# HallEffectSwitch.net
KiCad netlist of a schematic drawn in Altium Designer
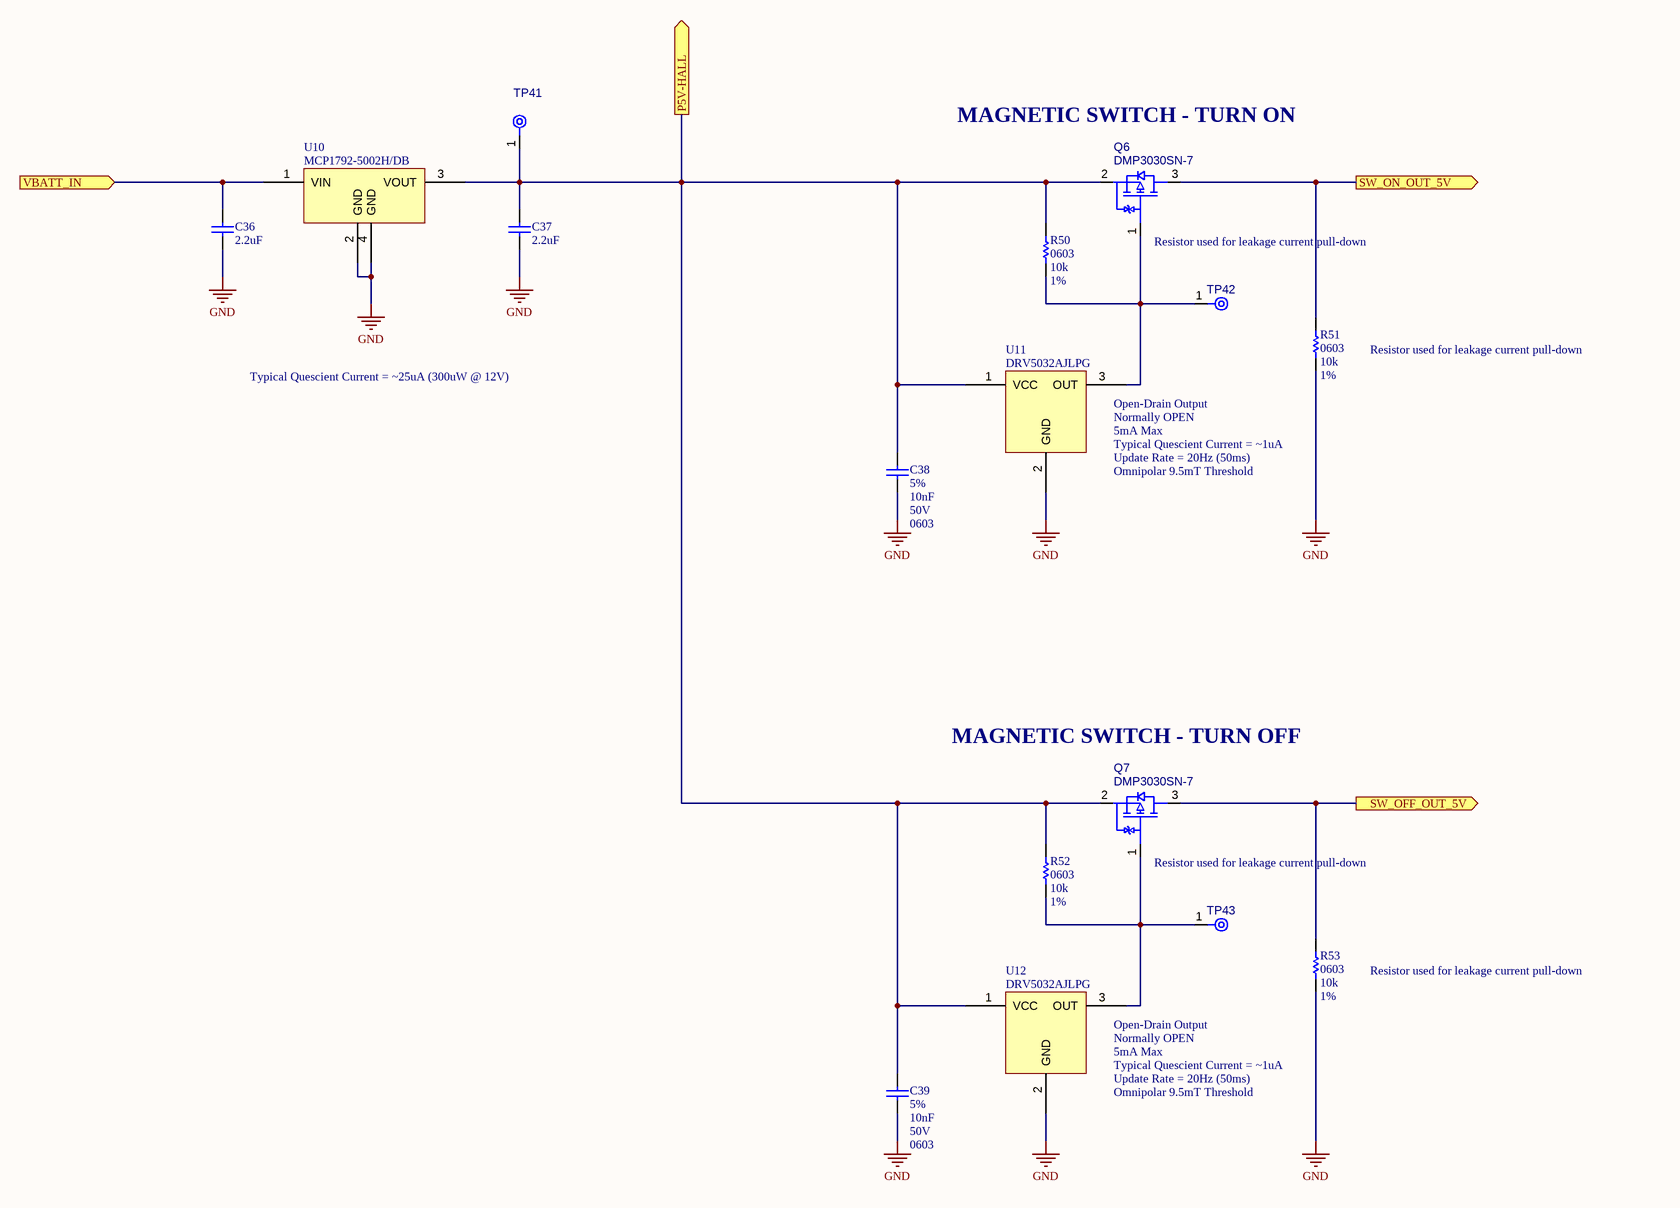
[diagram p0: HallEffectSwitch.SchDoc]

(export (version "E")
  (design (tool "Eeschema 10.0.6"))
  (components
    (comp (ref "C36")
      (value "2.2uF")
      (footprint "CAPC3225X270X30ML30")
      (description "Chip Capacitor, 2.2uF, 10%, 50 V, X7R 1210 (3225 Metric)")
      (fields (field (name "TOLERANCE") "10%") (field (name "Comment") "Capacitor 2.2uF 10%, 50V, X7R, 1210"))
      (libsource (lib "Applied Physics Lab") (part "CAP-NP-2"))
    )
    (comp (ref "C37")
      (value "2.2uF")
      (footprint "CAPC3225X270X30ML30")
      (description "Chip Capacitor, 2.2uF, 10%, 50 V, X7R 1210 (3225 Metric)")
      (fields (field (name "TOLERANCE") "10%") (field (name "Comment") "Capacitor 2.2uF 10%, 50V, X7R, 1210"))
      (libsource (lib "Applied Physics Lab") (part "CAP-NP-2"))
    )
    (comp (ref "C38")
      (value "10nF")
      (footprint "CAPC1608X90X40ML10T20")
      (description "Chip Capacitor, 10nF, +/- 5%, 50 V, C0G 0603 (1608 Metric)")
      (fields
        (field (name "TOLERANCE") "5%")
        (field (name "VOLTAGE RATING") "50V")
        (field (name "CASE/PACKAGE") "0603")
        (field (name "Comment") "Capacitor 10nF +/- 5%, 50V, C0G, 0603")
      )
      (libsource (lib "Applied Physics Lab") (part "CAP-NP-2"))
    )
    (comp (ref "C39")
      (value "10nF")
      (footprint "CAPC1608X90X40ML10T20")
      (description "Chip Capacitor, 10nF, +/- 5%, 50 V, C0G 0603 (1608 Metric)")
      (fields
        (field (name "TOLERANCE") "5%")
        (field (name "VOLTAGE RATING") "50V")
        (field (name "CASE/PACKAGE") "0603")
        (field (name "Comment") "Capacitor 10nF +/- 5%, 50V, C0G, 0603")
      )
      (libsource (lib "Applied Physics Lab") (part "CAP-NP-2"))
    )
    (comp (ref "Q6")
      (value "DMP3030SN-7")
      (footprint "SOT95P164X140-3M")
      (description "Trans Mosfet P-ch 30V 0.7A 3-PIN SC-59 T/r / Mosfet P-ch 30V 700MA SC59-3")
      (libsource (lib "Applied Physics Lab") (part "CMP-00006-6"))
    )
    (comp (ref "Q7")
      (value "DMP3030SN-7")
      (footprint "SOT95P164X140-3M")
      (description "Trans Mosfet P-ch 30V 0.7A 3-PIN SC-59 T/r / Mosfet P-ch 30V 700MA SC59-3")
      (libsource (lib "Applied Physics Lab") (part "CMP-00006-6"))
    )
    (comp (ref "R50")
      (value "10k")
      (footprint "RESC1608X55X25ML10T15")
      (description "Chip Resistor, 10 KOhm, +/- 1%, 01 W, -55 to 155 degC, 0603 (1608 Metric)")
      (fields
        (field (name "POWER") "100mW")
        (field (name "CASE/PACKAGE") "0603")
        (field (name "TOLERANCE") "1%")
        (field (name "Comment") "Resistor 10k +/-1% 0603 100 mW")
      )
      (libsource (lib "Applied Physics Lab") (part "RES-2"))
    )
    (comp (ref "R51")
      (value "10k")
      (footprint "RESC1608X55X25ML10T15")
      (description "Chip Resistor, 10 KOhm, +/- 1%, 01 W, -55 to 155 degC, 0603 (1608 Metric)")
      (fields
        (field (name "POWER") "100mW")
        (field (name "CASE/PACKAGE") "0603")
        (field (name "TOLERANCE") "1%")
        (field (name "Comment") "Resistor 10k +/-1% 0603 100 mW")
      )
      (libsource (lib "Applied Physics Lab") (part "RES-2"))
    )
    (comp (ref "R52")
      (value "10k")
      (footprint "RESC1608X55X25ML10T15")
      (description "Chip Resistor, 10 KOhm, +/- 1%, 01 W, -55 to 155 degC, 0603 (1608 Metric)")
      (fields
        (field (name "POWER") "100mW")
        (field (name "CASE/PACKAGE") "0603")
        (field (name "TOLERANCE") "1%")
        (field (name "Comment") "Resistor 10k +/-1% 0603 100 mW")
      )
      (libsource (lib "Applied Physics Lab") (part "RES-2"))
    )
    (comp (ref "R53")
      (value "10k")
      (footprint "RESC1608X55X25ML10T15")
      (description "Chip Resistor, 10 KOhm, +/- 1%, 01 W, -55 to 155 degC, 0603 (1608 Metric)")
      (fields
        (field (name "POWER") "100mW")
        (field (name "CASE/PACKAGE") "0603")
        (field (name "TOLERANCE") "1%")
        (field (name "Comment") "Resistor 10k +/-1% 0603 100 mW")
      )
      (libsource (lib "Applied Physics Lab") (part "RES-2"))
    )
    (comp (ref "TP41")
      (value "TPAD6R-CIRCLED")
      (footprint "TP06R - Circled")
      (description "0.6mm round with a silkscreen circle.")
      (libsource (lib "Applied Physics Lab") (part "CMP-001-0001-4"))
    )
    (comp (ref "TP42")
      (value "TPAD6R-CIRCLED")
      (footprint "TP06R - Circled")
      (description "0.6mm round with a silkscreen circle.")
      (libsource (lib "") (part "CMP-001-0001-4_1"))
    )
    (comp (ref "TP43")
      (value "TPAD6R-CIRCLED")
      (footprint "TP06R - Circled")
      (description "0.6mm round with a silkscreen circle.")
      (libsource (lib "") (part "CMP-001-0001-4_1"))
    )
    (comp (ref "U10")
      (value "MCP1792-5002H/DB")
      (footprint "SOT230P700X180-4M")
      (description "High input voltage regulator 5.0 V 3Ld SOT-223 3 SOT-223 TUBE RoHS Compliant: Yes")
      (libsource (lib "Applied Physics Lab") (part "MCP1792-5002H_DB-Symbol-1"))
    )
    (comp (ref "U11")
      (value "DRV5032AJLPG")
      (footprint "DRV5032ZELPGM - 500-92-US Lead Formed")
      (libsource (lib "Applied Physics Lab") (part "DRV5032ZELPGM-Symbol-1"))
    )
    (comp (ref "U12")
      (value "DRV5032AJLPG")
      (footprint "DRV5032ZELPGM - 500-92-US Lead Formed")
      (libsource (lib "Applied Physics Lab") (part "DRV5032ZELPGM-Symbol-1"))
    )
  )
  (nets
    (net (code "1") (name "/P5V-HALL") (class "Default")
      (node (ref "C37") (pin "2") (pinfunction "2_2") (pintype "passive"))
      (node (ref "C38") (pin "2") (pinfunction "2_2") (pintype "passive"))
      (node (ref "C39") (pin "2") (pinfunction "2_2") (pintype "passive"))
      (node (ref "Q6") (pin "2") (pinfunction "S_2") (pintype "passive"))
      (node (ref "Q7") (pin "2") (pinfunction "S_2") (pintype "passive"))
      (node (ref "R50") (pin "2") (pinfunction "2_2") (pintype "passive"))
      (node (ref "R52") (pin "2") (pinfunction "2_2") (pintype "passive"))
      (node (ref "TP41") (pin "1") (pinfunction "TP_1") (pintype "passive"))
      (node (ref "U10") (pin "3") (pinfunction "VOUT_3") (pintype "passive"))
      (node (ref "U11") (pin "1") (pinfunction "VCC_1") (pintype "passive"))
      (node (ref "U12") (pin "1") (pinfunction "VCC_1") (pintype "passive"))
    )
    (net (code "2") (name "/SW_OFF_OUT_5V") (class "Default")
      (node (ref "Q7") (pin "3") (pinfunction "D_3") (pintype "passive"))
      (node (ref "R53") (pin "2") (pinfunction "2_2") (pintype "passive"))
    )
    (net (code "3") (name "/SW_ON_OUT_5V") (class "Default")
      (node (ref "Q6") (pin "3") (pinfunction "D_3") (pintype "passive"))
      (node (ref "R51") (pin "2") (pinfunction "2_2") (pintype "passive"))
    )
    (net (code "4") (name "/VBATT_IN") (class "Default")
      (node (ref "C36") (pin "2") (pinfunction "2_2") (pintype "passive"))
      (node (ref "U10") (pin "1") (pinfunction "VIN_1") (pintype "passive"))
    )
    (net (code "5") (name "GND") (class "Default")
      (node (ref "C36") (pin "1") (pinfunction "1_1") (pintype "passive"))
      (node (ref "C37") (pin "1") (pinfunction "1_1") (pintype "passive"))
      (node (ref "C38") (pin "1") (pinfunction "1_1") (pintype "passive"))
      (node (ref "C39") (pin "1") (pinfunction "1_1") (pintype "passive"))
      (node (ref "R51") (pin "1") (pinfunction "1_1") (pintype "passive"))
      (node (ref "R53") (pin "1") (pinfunction "1_1") (pintype "passive"))
      (node (ref "U10") (pin "2") (pinfunction "GND_2") (pintype "passive"))
      (node (ref "U10") (pin "4") (pinfunction "GND_4") (pintype "passive"))
      (node (ref "U11") (pin "2") (pinfunction "GND_2") (pintype "passive"))
      (node (ref "U12") (pin "2") (pinfunction "GND_2") (pintype "passive"))
    )
    (net (code "6") (name "Net-(Q6-G)") (class "Default")
      (node (ref "Q6") (pin "1") (pinfunction "G_1") (pintype "passive"))
      (node (ref "R50") (pin "1") (pinfunction "1_1") (pintype "passive"))
      (node (ref "TP42") (pin "1") (pinfunction "TP_1") (pintype "passive"))
      (node (ref "U11") (pin "3") (pinfunction "OUT_3") (pintype "passive"))
    )
    (net (code "7") (name "Net-(Q7-G)") (class "Default")
      (node (ref "Q7") (pin "1") (pinfunction "G_1") (pintype "passive"))
      (node (ref "R52") (pin "1") (pinfunction "1_1") (pintype "passive"))
      (node (ref "TP43") (pin "1") (pinfunction "TP_1") (pintype "passive"))
      (node (ref "U12") (pin "3") (pinfunction "OUT_3") (pintype "passive"))
    )
  )
)
